# MotorDriverPCB.net
KiCad netlist of a schematic drawn in Altium Designer
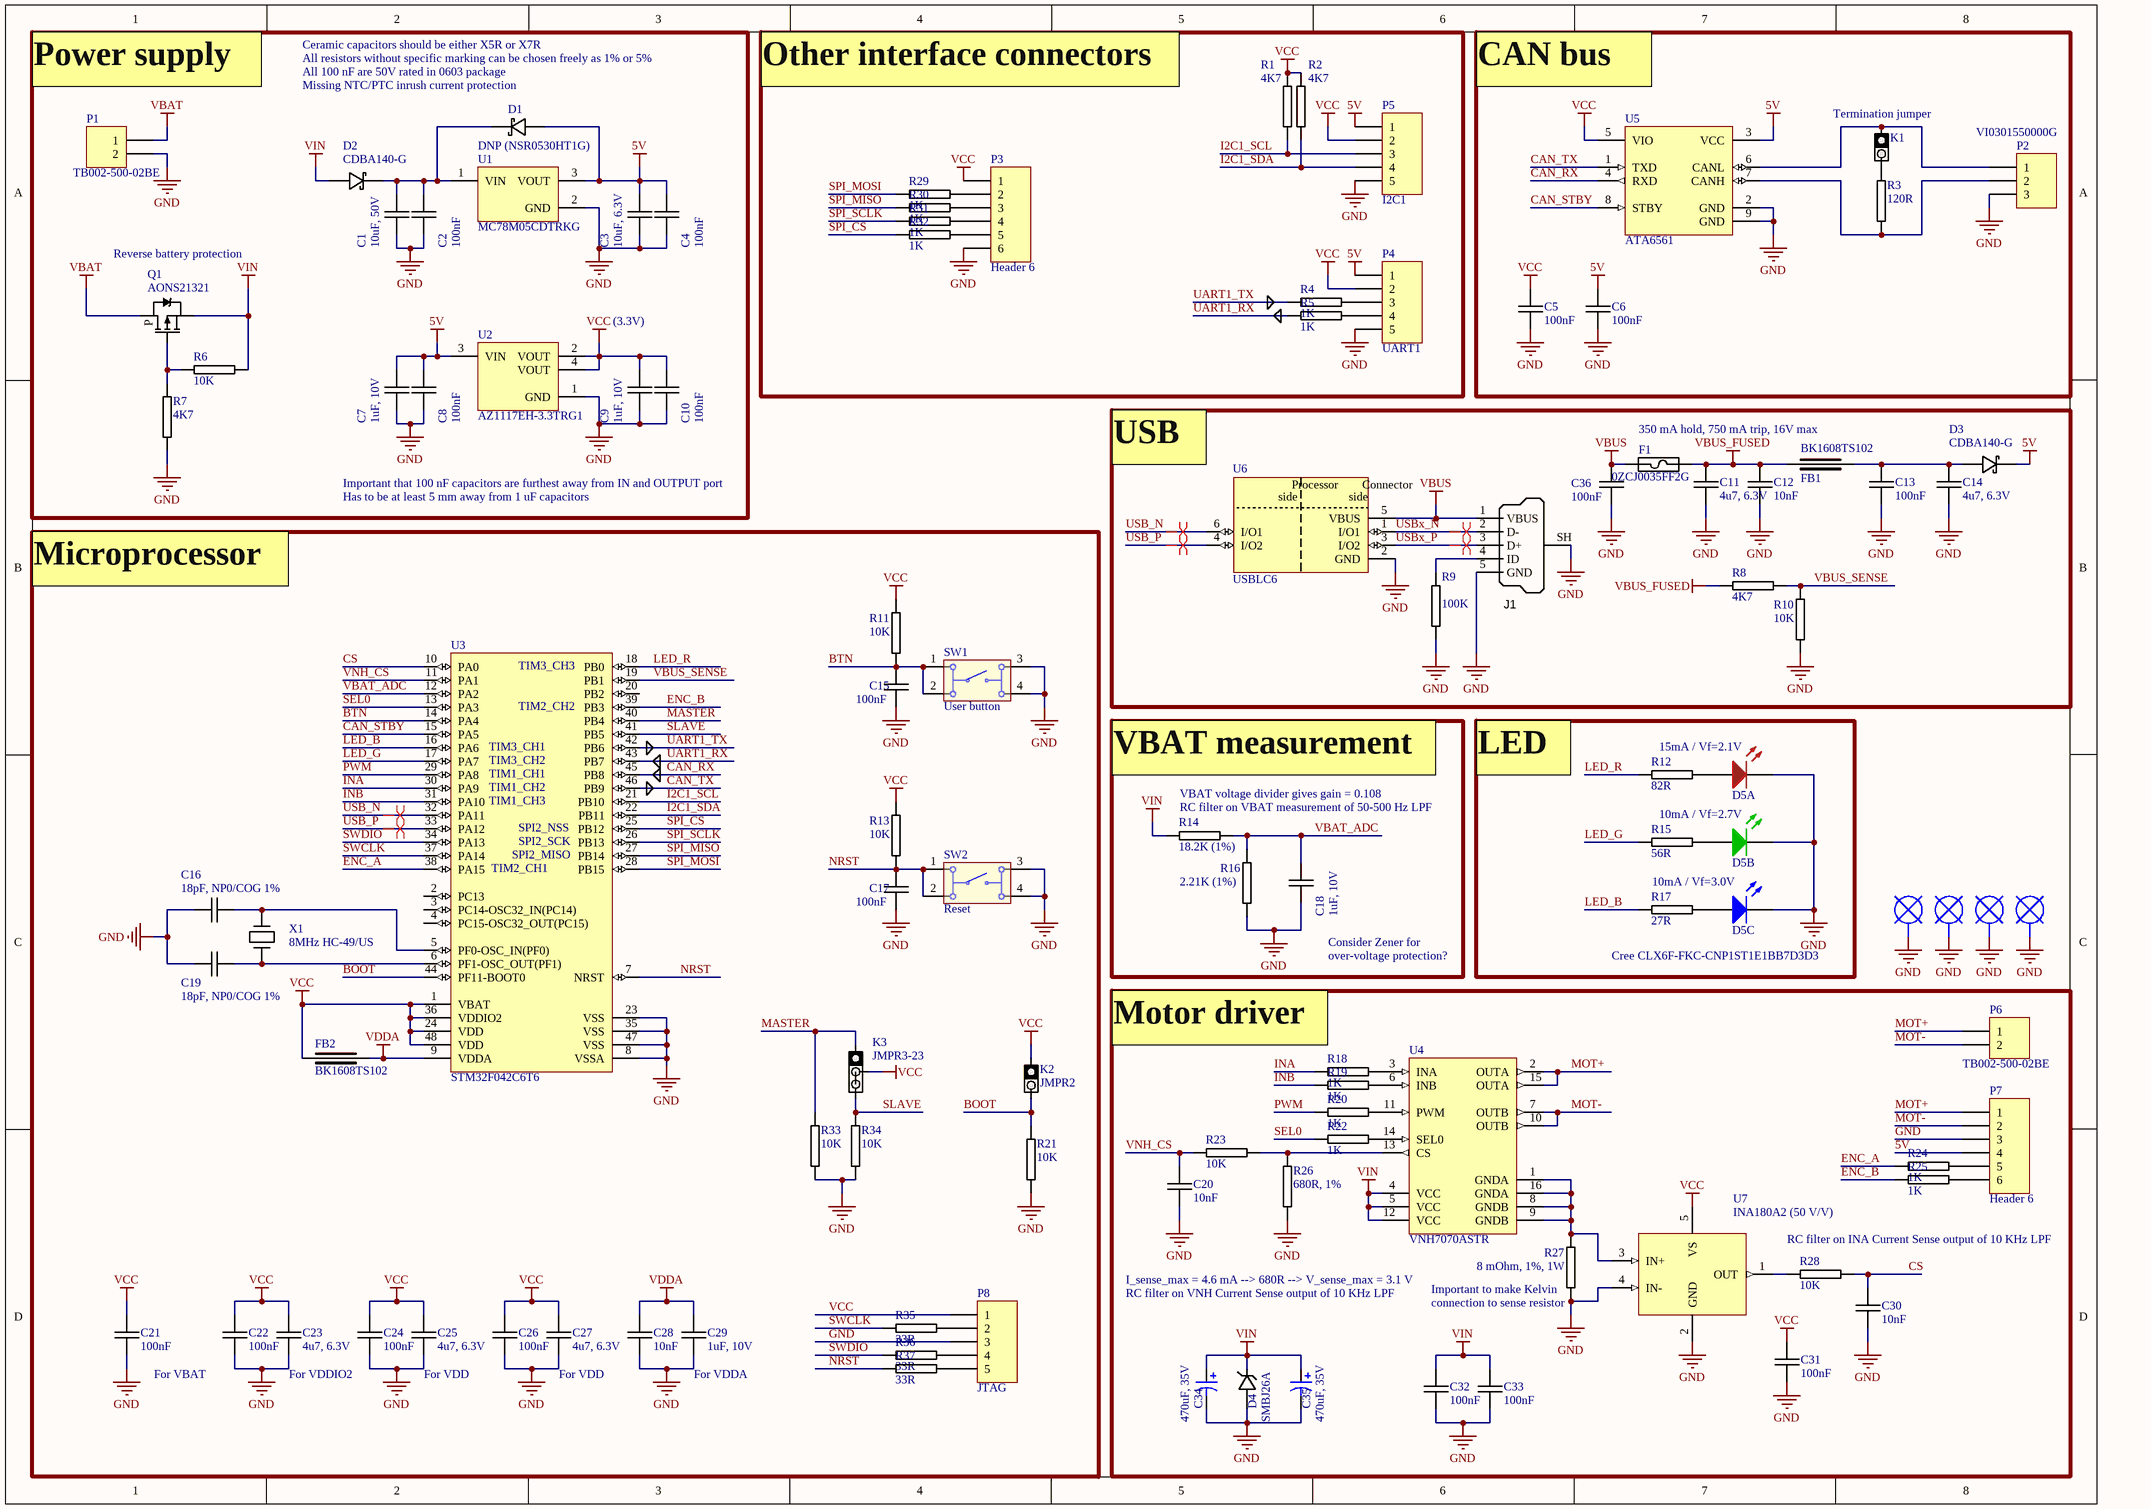
[diagram p0: MotorDriverPCB.SchDoc]

(export (version "E")
  (design (tool "Eeschema 10.0.6"))
  (components
    (comp (ref "C1")
      (value "10uF, 50V")
      (footprint "1206C-GENERIC")
      (description "CAP CER 10UF 35V Y5V 1206")
      (fields (field (name "MANUFACTURER PART NUMBER") "GMK316F106ZL-T"))
      (libsource (lib "vh_Altium Library") (part "1206C-10U-35V-X7R"))
    )
    (comp (ref "C2")
      (value "100nF")
      (footprint "0603C-GENERIC")
      (description "CAP CER .10UF 25V X7R 10% 0603")
      (fields (field (name "MANUFACTURER PART NUMBER") "C1608X7R1E104K"))
      (libsource (lib "vh_Altium Library") (part "0603C-100NF-25V-X7R-TDK"))
    )
    (comp (ref "C3")
      (value "10uF, 6.3V")
      (footprint "0805C-GENERIC")
      (description "CAP 10UF 6.3V CERAMIC X5R 0805")
      (fields (field (name "TOLERANCE") "±20%"))
      (libsource (lib "vh_Altium Library") (part "0805C-10UF-6V3-X5R-PAN"))
    )
    (comp (ref "C4")
      (value "100nF")
      (footprint "0603C-GENERIC")
      (description "CAP CER .10UF 25V X7R 10% 0603")
      (fields (field (name "MANUFACTURER PART NUMBER") "C1608X7R1E104K"))
      (libsource (lib "vh_Altium Library") (part "0603C-100NF-25V-X7R-TDK"))
    )
    (comp (ref "C5")
      (value "100nF")
      (footprint "0603C-GENERIC")
      (description "CAP CER .10UF 25V X7R 10% 0603")
      (fields (field (name "MANUFACTURER PART NUMBER") "C1608X7R1E104K"))
      (libsource (lib "vh_Altium Library") (part "0603C-100NF-25V-X7R-TDK"))
    )
    (comp (ref "C6")
      (value "100nF")
      (footprint "0603C-GENERIC")
      (description "CAP CER .10UF 25V X7R 10% 0603")
      (fields (field (name "MANUFACTURER PART NUMBER") "C1608X7R1E104K"))
      (libsource (lib "vh_Altium Library") (part "0603C-100NF-25V-X7R-TDK"))
    )
    (comp (ref "C7")
      (value "1uF, 10V")
      (footprint "0603C-GENERIC")
      (description "CAP CER 1.0UF 35V X5R 0603")
      (fields (field (name "MANUFACTURER PART NUMBER") "GMK107BJ105KA-T"))
      (libsource (lib "vh_Altium Library") (part "0603C-1UF-35V-X5R-TAY"))
    )
    (comp (ref "C8")
      (value "100nF")
      (footprint "0603C-GENERIC")
      (description "CAP CER .10UF 25V X7R 10% 0603")
      (fields (field (name "MANUFACTURER PART NUMBER") "C1608X7R1E104K"))
      (libsource (lib "vh_Altium Library") (part "0603C-100NF-25V-X7R-TDK"))
    )
    (comp (ref "C9")
      (value "1uF, 10V")
      (footprint "0603C-GENERIC")
      (description "CAP CER 1.0UF 35V X5R 0603")
      (fields (field (name "MANUFACTURER PART NUMBER") "GMK107BJ105KA-T"))
      (libsource (lib "vh_Altium Library") (part "0603C-1UF-35V-X5R-TAY"))
    )
    (comp (ref "C10")
      (value "100nF")
      (footprint "0603C-GENERIC")
      (description "CAP CER .10UF 25V X7R 10% 0603")
      (fields (field (name "MANUFACTURER PART NUMBER") "C1608X7R1E104K"))
      (libsource (lib "vh_Altium Library") (part "0603C-100NF-25V-X7R-TDK"))
    )
    (comp (ref "C11")
      (value "4u7, 6.3V")
      (footprint "0603C-GENERIC")
      (description "GENERIC CAPACITOR NON POLARISED 0603")
      (libsource (lib "vh_Altium Library") (part "0603C-4U7-6V3-X5R-KEM"))
    )
    (comp (ref "C12")
      (value "10nF")
      (footprint "0603C-GENERIC")
      (description "GENERIC CAPACITOR NON POLARISED 0603")
      (fields
        (field (name "MANUFACTURER PART NUMBER") "GRM188R71H103KA01D")
        (field (name "MANUFACTURER") "Murata Electronics North America")
      )
      (libsource (lib "vh_Altium Library") (part "0603C-10NF-50V-X7R-MUR"))
    )
    (comp (ref "C13")
      (value "100nF")
      (footprint "0603C-GENERIC")
      (description "CAP CER .10UF 25V X7R 10% 0603")
      (fields (field (name "MANUFACTURER PART NUMBER") "C1608X7R1E104K"))
      (libsource (lib "vh_Altium Library") (part "0603C-100NF-25V-X7R-TDK"))
    )
    (comp (ref "C14")
      (value "4u7, 6.3V")
      (footprint "0603C-GENERIC")
      (description "GENERIC CAPACITOR NON POLARISED 0603")
      (libsource (lib "vh_Altium Library") (part "0603C-4U7-6V3-X5R-KEM"))
    )
    (comp (ref "C15")
      (value "100nF")
      (footprint "0603C-GENERIC")
      (description "CAP CER .10UF 25V X7R 10% 0603")
      (fields (field (name "MANUFACTURER PART NUMBER") "C1608X7R1E104K"))
      (libsource (lib "vh_Altium Library") (part "0603C-100NF-25V-X7R-TDK"))
    )
    (comp (ref "C16")
      (value "18pF, NP0/COG 1%")
      (footprint "0603C-GENERIC")
      (description "GENERIC CAPACITOR NON POLARISED 0603")
      (libsource (lib "vh_Altium Library") (part "0603C-15PF-50V-C0G-MUR"))
    )
    (comp (ref "C17")
      (value "100nF")
      (footprint "0603C-GENERIC")
      (description "CAP CER .10UF 25V X7R 10% 0603")
      (fields (field (name "MANUFACTURER PART NUMBER") "C1608X7R1E104K"))
      (libsource (lib "vh_Altium Library") (part "0603C-100NF-25V-X7R-TDK"))
    )
    (comp (ref "C18")
      (value "1uF, 10V")
      (footprint "0603C-GENERIC")
      (description "CAP CER 1.0UF 35V X5R 0603")
      (fields (field (name "MANUFACTURER PART NUMBER") "GMK107BJ105KA-T"))
      (libsource (lib "vh_Altium Library") (part "0603C-1UF-35V-X5R-TAY"))
    )
    (comp (ref "C19")
      (value "18pF, NP0/COG 1%")
      (footprint "0603C-GENERIC")
      (description "GENERIC CAPACITOR NON POLARISED 0603")
      (libsource (lib "vh_Altium Library") (part "0603C-15PF-50V-C0G-MUR"))
    )
    (comp (ref "C20")
      (value "10nF")
      (footprint "0603C-GENERIC")
      (description "GENERIC CAPACITOR NON POLARISED 0603")
      (fields
        (field (name "MANUFACTURER PART NUMBER") "GRM188R71H103KA01D")
        (field (name "MANUFACTURER") "Murata Electronics North America")
      )
      (libsource (lib "vh_Altium Library") (part "0603C-10NF-50V-X7R-MUR"))
    )
    (comp (ref "C21")
      (value "100nF")
      (footprint "0603C-GENERIC")
      (description "CAP CER .10UF 25V X7R 10% 0603")
      (fields (field (name "MANUFACTURER PART NUMBER") "C1608X7R1E104K"))
      (libsource (lib "vh_Altium Library") (part "0603C-100NF-25V-X7R-TDK"))
    )
    (comp (ref "C22")
      (value "100nF")
      (footprint "0603C-GENERIC")
      (description "CAP CER .10UF 25V X7R 10% 0603")
      (fields (field (name "MANUFACTURER PART NUMBER") "C1608X7R1E104K"))
      (libsource (lib "vh_Altium Library") (part "0603C-100NF-25V-X7R-TDK"))
    )
    (comp (ref "C23")
      (value "4u7, 6.3V")
      (footprint "0603C-GENERIC")
      (description "GENERIC CAPACITOR NON POLARISED 0603")
      (libsource (lib "vh_Altium Library") (part "0603C-4U7-6V3-X5R-KEM"))
    )
    (comp (ref "C24")
      (value "100nF")
      (footprint "0603C-GENERIC")
      (description "CAP CER .10UF 25V X7R 10% 0603")
      (fields (field (name "MANUFACTURER PART NUMBER") "C1608X7R1E104K"))
      (libsource (lib "vh_Altium Library") (part "0603C-100NF-25V-X7R-TDK"))
    )
    (comp (ref "C25")
      (value "4u7, 6.3V")
      (footprint "0603C-GENERIC")
      (description "GENERIC CAPACITOR NON POLARISED 0603")
      (libsource (lib "vh_Altium Library") (part "0603C-4U7-6V3-X5R-KEM"))
    )
    (comp (ref "C26")
      (value "100nF")
      (footprint "0603C-GENERIC")
      (description "CAP CER .10UF 25V X7R 10% 0603")
      (fields (field (name "MANUFACTURER PART NUMBER") "C1608X7R1E104K"))
      (libsource (lib "vh_Altium Library") (part "0603C-100NF-25V-X7R-TDK"))
    )
    (comp (ref "C27")
      (value "4u7, 6.3V")
      (footprint "0603C-GENERIC")
      (description "GENERIC CAPACITOR NON POLARISED 0603")
      (libsource (lib "vh_Altium Library") (part "0603C-4U7-6V3-X5R-KEM"))
    )
    (comp (ref "C28")
      (value "10nF")
      (footprint "0603C-GENERIC")
      (description "GENERIC CAPACITOR NON POLARISED 0603")
      (fields
        (field (name "MANUFACTURER PART NUMBER") "GRM188R71H103KA01D")
        (field (name "MANUFACTURER") "Murata Electronics North America")
      )
      (libsource (lib "vh_Altium Library") (part "0603C-10NF-50V-X7R-MUR"))
    )
    (comp (ref "C29")
      (value "1uF, 10V")
      (footprint "0603C-GENERIC")
      (description "CAP CER 1.0UF 35V X5R 0603")
      (fields (field (name "MANUFACTURER PART NUMBER") "GMK107BJ105KA-T"))
      (libsource (lib "vh_Altium Library") (part "0603C-1UF-35V-X5R-TAY"))
    )
    (comp (ref "C30")
      (value "10nF")
      (footprint "0603C-GENERIC")
      (description "GENERIC CAPACITOR NON POLARISED 0603")
      (fields
        (field (name "MANUFACTURER PART NUMBER") "GRM188R71H103KA01D")
        (field (name "MANUFACTURER") "Murata Electronics North America")
      )
      (libsource (lib "vh_Altium Library") (part "0603C-10NF-50V-X7R-MUR"))
    )
    (comp (ref "C31")
      (value "100nF")
      (footprint "0603C-GENERIC")
      (description "CAP CER .10UF 25V X7R 10% 0603")
      (fields (field (name "MANUFACTURER PART NUMBER") "C1608X7R1E104K"))
      (libsource (lib "vh_Altium Library") (part "0603C-100NF-25V-X7R-TDK"))
    )
    (comp (ref "C32")
      (value "100nF")
      (footprint "0603C-GENERIC")
      (description "CAP CER .10UF 25V X7R 10% 0603")
      (fields (field (name "MANUFACTURER PART NUMBER") "C1608X7R1E104K"))
      (libsource (lib "vh_Altium Library") (part "0603C-100NF-25V-X7R-TDK"))
    )
    (comp (ref "C33")
      (value "100nF")
      (footprint "0603C-GENERIC")
      (description "CAP CER .10UF 25V X7R 10% 0603")
      (fields (field (name "MANUFACTURER PART NUMBER") "C1608X7R1E104K"))
      (libsource (lib "vh_Altium Library") (part "0603C-100NF-25V-X7R-TDK"))
    )
    (comp (ref "C34")
      (value "470uF, 35V")
      (footprint "SMT_10x10.5")
      (description "Surface mount, Polarized Electrolytic Aluminum Capacitor")
      (libsource (lib "AluminumCapacitors") (part "AluCap_SMT"))
    )
    (comp (ref "C35")
      (value "470uF, 35V")
      (footprint "SMT_10x10.5")
      (description "Surface mount, Polarized Electrolytic Aluminum Capacitor")
      (libsource (lib "AluminumCapacitors") (part "AluCap_SMT"))
    )
    (comp (ref "C36")
      (value "100nF")
      (footprint "0603C-GENERIC")
      (description "CAP CER .10UF 25V X7R 10% 0603")
      (fields (field (name "MANUFACTURER PART NUMBER") "C1608X7R1E104K"))
      (libsource (lib "vh_Altium Library") (part "0603C-100NF-25V-X7R-TDK"))
    )
    (comp (ref "D1")
      (value "DNP (NSR0530HT1G)")
      (footprint "SOD323")
      (description "Diode Schottky")
      (libsource (lib "Components") (part "DIODE_SCHOTTKY"))
    )
    (comp (ref "D2")
      (value "CDBA140-G")
      (footprint "DO-214AC-SMA")
      (description "Diode Schottky")
      (libsource (lib "Components") (part "DIODE_SCHOTTKY"))
    )
    (comp (ref "D3")
      (value "CDBA140-G")
      (footprint "DO-214AC-SMA")
      (description "Diode Schottky")
      (libsource (lib "Components") (part "DIODE_SCHOTTKY"))
    )
    (comp (ref "D4")
      (value "SMBJ26A")
      (footprint "DO-214AA")
      (description "Diode SMD Transil")
      (libsource (lib "Components") (part "DIODE_TVS"))
    )
    (comp (ref "D5")
      (value "LED RGB Individual")
      (footprint "LED-3535-6")
      (libsource (lib "Components") (part "LED RGB Individual"))
    )
    (comp (ref "F1")
      (value "0ZCJ0035FF2G")
      (footprint "1206C-GENERIC")
      (description "PTC Resettable Fuse")
      (libsource (lib "Components") (part "FUSE-PTC"))
    )
    (comp (ref "FB1")
      (value "BK1608TS102")
      (footprint "0603FB-GENERIC")
      (description "FERRITE BEAD SMD")
      (libsource (lib "vh_Altium Library") (part "0603FB-GENERIC"))
    )
    (comp (ref "FB2")
      (value "BK1608TS102")
      (footprint "0603FB-GENERIC")
      (description "FERRITE BEAD SMD")
      (libsource (lib "vh_Altium Library") (part "0603FB-GENERIC"))
    )
    (comp (ref "H1")
      (value "SCREW-HOLE")
      (footprint "Screw-hole-3mm")
      (description "PCB Screw hole")
      (libsource (lib "Components") (part "SCREW-HOLE"))
    )
    (comp (ref "H2")
      (value "SCREW-HOLE")
      (footprint "Screw-hole-3mm")
      (description "PCB Screw hole")
      (libsource (lib "Components") (part "SCREW-HOLE"))
    )
    (comp (ref "H3")
      (value "SCREW-HOLE")
      (footprint "Screw-hole-3mm")
      (description "PCB Screw hole")
      (libsource (lib "Components") (part "SCREW-HOLE"))
    )
    (comp (ref "H4")
      (value "SCREW-HOLE")
      (footprint "Screw-hole-3mm")
      (description "PCB Screw hole")
      (libsource (lib "Components") (part "SCREW-HOLE"))
    )
    (comp (ref "J1")
      (value "USB Type B")
      (footprint "USB-MINI-B")
      (description "Connector SMD-THD USB Type B middle mount")
      (libsource (lib "Components") (part "USB-Type-B"))
    )
    (comp (ref "K1")
      (value "JMPR2")
      (footprint "JMPR2")
      (description "CONN HEADER .100 SINGL STR 36POS")
      (fields (field (name "MANUFACTURER") "Sullins Connector Solutions"))
      (libsource (lib "vh_Altium Library") (part "JMPR2"))
    )
    (comp (ref "K2")
      (value "JMPR2")
      (footprint "JMPR2")
      (description "CONN HEADER .100 SINGL STR 36POS")
      (fields (field (name "MANUFACTURER") "Sullins Connector Solutions"))
      (libsource (lib "vh_Altium Library") (part "JMPR2"))
    )
    (comp (ref "K3")
      (value "JMPR3-23")
      (footprint "JMPR3-CLOSED-23")
      (description "CONN HEADER .100 SINGL STR 36POS")
      (fields (field (name "MANUFACTURER") "Sullins Connector Solutions"))
      (libsource (lib "vh_Altium Library") (part "JMPR3-23"))
    )
    (comp (ref "P1")
      (value "TB002-500-02BE")
      (footprint "SCREW-2-5mm")
      (description "Screw terminal, 2-pin, 5mm pitch")
      (libsource (lib "") (part "SCREW-2_1"))
    )
    (comp (ref "P2")
      (value "VI0301550000G")
      (footprint "SCREW-3-5mm")
      (description "Screw terminal, 3-pin, 5mm pitch")
      (libsource (lib "Components") (part "SCREW-3"))
    )
    (comp (ref "P3")
      (value "Header 6")
      (footprint "HEADER-1X6")
      (description "Header, 6-Pin")
      (fields (field (name "PUBLISHER") "Altium Limited"))
      (libsource (lib "Components") (part "Header 6"))
    )
    (comp (ref "P4")
      (value "UART1")
      (footprint "HEADER-1X5")
      (description "Header, 5-Pin")
      (libsource (lib "Components") (part "Header 5"))
    )
    (comp (ref "P5")
      (value "I2C1")
      (footprint "HEADER-1X5")
      (description "Header, 5-Pin")
      (libsource (lib "Components") (part "Header 5"))
    )
    (comp (ref "P6")
      (value "TB002-500-02BE")
      (footprint "SCREW-2-5mm")
      (description "Screw terminal, 2-pin, 5mm pitch")
      (libsource (lib "Components") (part "SCREW-2"))
    )
    (comp (ref "P7")
      (value "Header 6")
      (footprint "HEADER-1X6")
      (description "Header, 6-Pin")
      (fields (field (name "PUBLISHER") "Altium Limited"))
      (libsource (lib "Components") (part "Header 6"))
    )
    (comp (ref "P8")
      (value "JTAG")
      (footprint "HEADER-1X5")
      (description "Header, 5-Pin")
      (libsource (lib "Components") (part "Header 5"))
    )
    (comp (ref "Q1")
      (value "AONS21321")
      (footprint "SO8FL-DFN5x6")
      (description "P-Channel MOSFET")
      (fields (field (name "PUBLISHER") "Altium Limited"))
      (libsource (lib "Components") (part "MOSFET-P"))
    )
    (comp (ref "R1")
      (value "4K7")
      (footprint "0603R-4K7")
      (description "GENERIC RESISTOR 0603")
      (fields
        (field (name "MANUFACTURER") "Stackpole Electronics Inc")
        (field (name "MANUFACTURER PART NUMBER") "RMCF 1/16 4.7K 1% R")
      )
      (libsource (lib "vh_Altium Library") (part "0603R-4K7"))
    )
    (comp (ref "R2")
      (value "4K7")
      (footprint "0603R-4K7")
      (description "GENERIC RESISTOR 0603")
      (fields
        (field (name "MANUFACTURER") "Stackpole Electronics Inc")
        (field (name "MANUFACTURER PART NUMBER") "RMCF 1/16 4.7K 1% R")
      )
      (libsource (lib "vh_Altium Library") (part "0603R-4K7"))
    )
    (comp (ref "R3")
      (value "120R")
      (footprint "0603R-120")
      (description "RES TF 1/10W 120 OHM 1% 0603")
      (fields (field (name "TOLERANCE") "±1%"))
      (libsource (lib "vh_Altium Library") (part "0603R-120"))
    )
    (comp (ref "R4")
      (value "1K")
      (footprint "0603R-1k")
      (description "GENERIC RESISTOR 0603")
      (fields
        (field (name "MANUFACTURER PART NUMBER") "RMCF 1/16 1K 1% R")
        (field (name "MANUFACTURER") "Stackpole Electronics Inc")
      )
      (libsource (lib "vh_Altium Library") (part "0603R-1K"))
    )
    (comp (ref "R5")
      (value "1K")
      (footprint "0603R-1k")
      (description "GENERIC RESISTOR 0603")
      (fields
        (field (name "MANUFACTURER PART NUMBER") "RMCF 1/16 1K 1% R")
        (field (name "MANUFACTURER") "Stackpole Electronics Inc")
      )
      (libsource (lib "vh_Altium Library") (part "0603R-1K"))
    )
    (comp (ref "R6")
      (value "10K")
      (footprint "0603R-10K")
      (description "GENERIC RESISTOR 0603")
      (fields (field (name "MANUFACTURER") "Stackpole Electronics Inc") (field (name "TOLERANCE") "±1%"))
      (libsource (lib "vh_Altium Library") (part "0603R-10K"))
    )
    (comp (ref "R7")
      (value "4K7")
      (footprint "0603R-4K7")
      (description "GENERIC RESISTOR 0603")
      (fields
        (field (name "MANUFACTURER") "Stackpole Electronics Inc")
        (field (name "MANUFACTURER PART NUMBER") "RMCF 1/16 4.7K 1% R")
      )
      (libsource (lib "vh_Altium Library") (part "0603R-4K7"))
    )
    (comp (ref "R8")
      (value "4K7")
      (footprint "0603R-4K7")
      (description "GENERIC RESISTOR 0603")
      (fields
        (field (name "MANUFACTURER") "Stackpole Electronics Inc")
        (field (name "MANUFACTURER PART NUMBER") "RMCF 1/16 4.7K 1% R")
      )
      (libsource (lib "vh_Altium Library") (part "0603R-4K7"))
    )
    (comp (ref "R9")
      (value "100K")
      (footprint "0603R-100K")
      (description "GENERIC RESISTOR 0603")
      (fields
        (field (name "TOLERANCE") "±1%")
        (field (name "MANUFACTURER PART NUMBER") "RMCF 1/16 100K 1% R")
      )
      (libsource (lib "vh_Altium Library") (part "0603R-100K"))
    )
    (comp (ref "R10")
      (value "10K")
      (footprint "0603R-10K")
      (description "GENERIC RESISTOR 0603")
      (fields (field (name "MANUFACTURER") "Stackpole Electronics Inc") (field (name "TOLERANCE") "±1%"))
      (libsource (lib "vh_Altium Library") (part "0603R-10K"))
    )
    (comp (ref "R11")
      (value "10K")
      (footprint "0603R-10K")
      (description "GENERIC RESISTOR 0603")
      (fields (field (name "MANUFACTURER") "Stackpole Electronics Inc") (field (name "TOLERANCE") "±1%"))
      (libsource (lib "vh_Altium Library") (part "0603R-10K"))
    )
    (comp (ref "R12")
      (value "82R")
      (footprint "0603R-82")
      (description "GENERIC RESISTOR 0603")
      (fields
        (field (name "MANUFACTURER") "Stackpole Electronics Inc")
        (field (name "MANUFACTURER PART NUMBER") "RMC 1/16 82 1% R")
      )
      (libsource (lib "vh_Altium Library") (part "0603R-82R"))
    )
    (comp (ref "R13")
      (value "10K")
      (footprint "0603R-10K")
      (description "GENERIC RESISTOR 0603")
      (fields (field (name "MANUFACTURER") "Stackpole Electronics Inc") (field (name "TOLERANCE") "±1%"))
      (libsource (lib "vh_Altium Library") (part "0603R-10K"))
    )
    (comp (ref "R14")
      (value "18.2K (1%)")
      (footprint "0603R-18K")
      (description "GENERIC RESISTOR 0603")
      (fields (field (name "TOLERANCE") "±1%") (field (name "MANUFACTURER PART NUMBER") "RMC 1/16 18K 1% R"))
      (libsource (lib "vh_Altium Library") (part "0603R-18K"))
    )
    (comp (ref "R15")
      (value "56R")
      (footprint "0603R-56")
      (description "GENERIC RESISTOR 0603")
      (fields
        (field (name "MANUFACTURER") "Stackpole Electronics Inc")
        (field (name "MANUFACTURER PART NUMBER") "RMC 1/16 56 1% R")
      )
      (libsource (lib "vh_Altium Library") (part "0603R-56R"))
    )
    (comp (ref "R16")
      (value "2.21K (1%)")
      (footprint "0603R-2K2")
      (description "RES TF 1/10W 2.2K OHM 1% 0603")
      (fields (field (name "MANUFACTURER PART NUMBER") "RMC 1/16 2.2K 1% R"))
      (libsource (lib "vh_Altium Library") (part "0603R-2K2"))
    )
    (comp (ref "R17")
      (value "27R")
      (footprint "0603R-27")
      (description "RES TF 1/10W 27 OHM 1% 0603")
      (fields (field (name "TOLERANCE") "±1%"))
      (libsource (lib "vh_Altium Library") (part "0603R-27R"))
    )
    (comp (ref "R18")
      (value "1K")
      (footprint "0603R-1k")
      (description "GENERIC RESISTOR 0603")
      (fields
        (field (name "MANUFACTURER PART NUMBER") "RMCF 1/16 1K 1% R")
        (field (name "MANUFACTURER") "Stackpole Electronics Inc")
      )
      (libsource (lib "vh_Altium Library") (part "0603R-1K"))
    )
    (comp (ref "R19")
      (value "1K")
      (footprint "0603R-1k")
      (description "GENERIC RESISTOR 0603")
      (fields
        (field (name "MANUFACTURER PART NUMBER") "RMCF 1/16 1K 1% R")
        (field (name "MANUFACTURER") "Stackpole Electronics Inc")
      )
      (libsource (lib "vh_Altium Library") (part "0603R-1K"))
    )
    (comp (ref "R20")
      (value "1K")
      (footprint "0603R-1k")
      (description "GENERIC RESISTOR 0603")
      (fields
        (field (name "MANUFACTURER PART NUMBER") "RMCF 1/16 1K 1% R")
        (field (name "MANUFACTURER") "Stackpole Electronics Inc")
      )
      (libsource (lib "vh_Altium Library") (part "0603R-1K"))
    )
    (comp (ref "R21")
      (value "10K")
      (footprint "0603R-10K")
      (description "GENERIC RESISTOR 0603")
      (fields (field (name "MANUFACTURER") "Stackpole Electronics Inc") (field (name "TOLERANCE") "±1%"))
      (libsource (lib "vh_Altium Library") (part "0603R-10K"))
    )
    (comp (ref "R22")
      (value "1K")
      (footprint "0603R-1k")
      (description "GENERIC RESISTOR 0603")
      (fields
        (field (name "MANUFACTURER PART NUMBER") "RMCF 1/16 1K 1% R")
        (field (name "MANUFACTURER") "Stackpole Electronics Inc")
      )
      (libsource (lib "vh_Altium Library") (part "0603R-1K"))
    )
    (comp (ref "R23")
      (value "10K")
      (footprint "0603R-10K")
      (description "GENERIC RESISTOR 0603")
      (fields (field (name "MANUFACTURER") "Stackpole Electronics Inc") (field (name "TOLERANCE") "±1%"))
      (libsource (lib "vh_Altium Library") (part "0603R-10K"))
    )
    (comp (ref "R24")
      (value "1K")
      (footprint "0603R-1k")
      (description "GENERIC RESISTOR 0603")
      (fields
        (field (name "MANUFACTURER PART NUMBER") "RMCF 1/16 1K 1% R")
        (field (name "MANUFACTURER") "Stackpole Electronics Inc")
      )
      (libsource (lib "vh_Altium Library") (part "0603R-1K"))
    )
    (comp (ref "R25")
      (value "1K")
      (footprint "0603R-1k")
      (description "GENERIC RESISTOR 0603")
      (fields
        (field (name "MANUFACTURER PART NUMBER") "RMCF 1/16 1K 1% R")
        (field (name "MANUFACTURER") "Stackpole Electronics Inc")
      )
      (libsource (lib "vh_Altium Library") (part "0603R-1K"))
    )
    (comp (ref "R26")
      (value "680R, 1%")
      (footprint "0603R-680")
      (description "RES TF 1/10W 680 OHM 1% 0603")
      (fields (field (name "MANUFACTURER PART NUMBER") "RMC 1/16 680 1% R"))
      (libsource (lib "vh_Altium Library") (part "0603R-680"))
    )
    (comp (ref "R27")
      (value "8 mOhm, 1%, 1W")
      (footprint "2512R-GENERIC")
      (description "POWER RESISTOR 2512")
      (libsource (lib "Components") (part "2512R"))
    )
    (comp (ref "R28")
      (value "10K")
      (footprint "0603R-10K")
      (description "GENERIC RESISTOR 0603")
      (fields (field (name "MANUFACTURER") "Stackpole Electronics Inc") (field (name "TOLERANCE") "±1%"))
      (libsource (lib "vh_Altium Library") (part "0603R-10K"))
    )
    (comp (ref "R29")
      (value "1K")
      (footprint "0603R-1k")
      (description "GENERIC RESISTOR 0603")
      (fields
        (field (name "MANUFACTURER PART NUMBER") "RMCF 1/16 1K 1% R")
        (field (name "MANUFACTURER") "Stackpole Electronics Inc")
      )
      (libsource (lib "vh_Altium Library") (part "0603R-1K"))
    )
    (comp (ref "R30")
      (value "1K")
      (footprint "0603R-1k")
      (description "GENERIC RESISTOR 0603")
      (fields
        (field (name "MANUFACTURER PART NUMBER") "RMCF 1/16 1K 1% R")
        (field (name "MANUFACTURER") "Stackpole Electronics Inc")
      )
      (libsource (lib "vh_Altium Library") (part "0603R-1K"))
    )
    (comp (ref "R31")
      (value "1K")
      (footprint "0603R-1k")
      (description "GENERIC RESISTOR 0603")
      (fields
        (field (name "MANUFACTURER PART NUMBER") "RMCF 1/16 1K 1% R")
        (field (name "MANUFACTURER") "Stackpole Electronics Inc")
      )
      (libsource (lib "vh_Altium Library") (part "0603R-1K"))
    )
    (comp (ref "R32")
      (value "1K")
      (footprint "0603R-1k")
      (description "GENERIC RESISTOR 0603")
      (fields
        (field (name "MANUFACTURER PART NUMBER") "RMCF 1/16 1K 1% R")
        (field (name "MANUFACTURER") "Stackpole Electronics Inc")
      )
      (libsource (lib "vh_Altium Library") (part "0603R-1K"))
    )
    (comp (ref "R33")
      (value "10K")
      (footprint "0603R-10K")
      (description "GENERIC RESISTOR 0603")
      (fields (field (name "MANUFACTURER") "Stackpole Electronics Inc") (field (name "TOLERANCE") "±1%"))
      (libsource (lib "vh_Altium Library") (part "0603R-10K"))
    )
    (comp (ref "R34")
      (value "10K")
      (footprint "0603R-10K")
      (description "GENERIC RESISTOR 0603")
      (fields (field (name "MANUFACTURER") "Stackpole Electronics Inc") (field (name "TOLERANCE") "±1%"))
      (libsource (lib "vh_Altium Library") (part "0603R-10K"))
    )
    (comp (ref "R35")
      (value "33R")
      (footprint "0603R-33")
      (description "RES TF 1/10W 33 OHM 1% 0603")
      (fields (field (name "MANUFACTURER PART NUMBER") "RMC 1/16 33 1% G"))
      (libsource (lib "vh_Altium Library") (part "0603R-33"))
    )
    (comp (ref "R36")
      (value "33R")
      (footprint "0603R-33")
      (description "RES TF 1/10W 33 OHM 1% 0603")
      (fields (field (name "MANUFACTURER PART NUMBER") "RMC 1/16 33 1% G"))
      (libsource (lib "vh_Altium Library") (part "0603R-33"))
    )
    (comp (ref "R37")
      (value "33R")
      (footprint "0603R-33")
      (description "RES TF 1/10W 33 OHM 1% 0603")
      (fields (field (name "MANUFACTURER PART NUMBER") "RMC 1/16 33 1% G"))
      (libsource (lib "vh_Altium Library") (part "0603R-33"))
    )
    (comp (ref "SW1")
      (value "User button")
      (footprint "TACT-TH-6x6")
      (description "Tactile Switch")
      (libsource (lib "Components") (part "Tactile Switch"))
    )
    (comp (ref "SW2")
      (value "Reset")
      (footprint "TACT-TH-6x6")
      (description "Tactile Switch")
      (libsource (lib "Components") (part "Tactile Switch"))
    )
    (comp (ref "U1")
      (value "MC78M05CDTRKG")
      (footprint "DPAK")
      (description "5V, 500mA, LDO Regulator, 3-Pin DDPAK")
      (libsource (lib "Components") (part "MC78M05CDTRKG"))
    )
    (comp (ref "U2")
      (value "AZ1117EH-3.3TRG1")
      (footprint "SOT-223")
      (description "3.3V, 1A, LDO Regulator, 3-Pin SOT-223")
      (libsource (lib "Components") (part "AZ1117EH-3.3TRG1"))
    )
    (comp (ref "U3")
      (value "STM32F042C6T6")
      (footprint "STM-LQFP48_N")
      (description "IC MCU 32BIT 32KB FLASH 48LQFP")
      (libsource (lib "Components") (part "STM32F042C6T6"))
    )
    (comp (ref "U4")
      (value "VNH7070ASTR")
      (footprint "STM-SO-16N_M")
      (description "SO 16 .15 TO JEDEC MS-012")
      (libsource (lib "Components") (part "VNH7070ASTR"))
    )
    (comp (ref "U5")
      (value "ATA6561")
      (footprint "VDFN8")
      (description "High-Speed CAN Transceiver with Standby Mode  CAN FD Ready")
      (libsource (lib "Components") (part "ATA6561"))
    )
    (comp (ref "U6")
      (value "USBLC6")
      (footprint "SOT23-6")
      (description "Very low capacitance ESD protection")
      (libsource (lib "Components") (part "USBLC6"))
    )
    (comp (ref "U7")
      (value "INA180A2 (50 V/V)")
      (footprint "SOT23-5")
      (description "INAx180 Low- and high-side voltage output, current-sense amplifiers")
      (libsource (lib "Components") (part "INA180A"))
    )
    (comp (ref "X1")
      (value "8MHz HC-49/US")
      (footprint "HC-49/US")
      (description "HC-49/US")
      (libsource (lib "Components") (part "HC-49/US"))
    )
  )
  (nets
    (net (code "1") (name "/BOOT") (class "Default")
      (node (ref "K2") (pin "2") (pintype "passive"))
      (node (ref "R21") (pin "2") (pintype "passive"))
      (node (ref "U3") (pin "44") (pinfunction "PF11-BOOT0_44") (pintype "bidirectional"))
    )
    (net (code "2") (name "/BTN") (class "Default")
      (node (ref "C15") (pin "1") (pintype "passive"))
      (node (ref "R11") (pin "1") (pintype "passive"))
      (node (ref "SW1") (pin "1") (pinfunction "1_1") (pintype "passive"))
      (node (ref "SW1") (pin "2") (pinfunction "2_2") (pintype "passive"))
      (node (ref "U3") (pin "14") (pinfunction "PA4_14") (pintype "bidirectional"))
    )
    (net (code "3") (name "/CAN_RX") (class "Default")
      (node (ref "U3") (pin "45") (pinfunction "PB8_45") (pintype "bidirectional"))
      (node (ref "U5") (pin "4") (pinfunction "RXD_4") (pintype "output"))
    )
    (net (code "4") (name "/CAN_STBY") (class "Default")
      (node (ref "U3") (pin "15") (pinfunction "PA5_15") (pintype "bidirectional"))
      (node (ref "U5") (pin "8") (pinfunction "STBY_8") (pintype "input"))
    )
    (net (code "5") (name "/CAN_TX") (class "Default")
      (node (ref "U3") (pin "46") (pinfunction "PB9_46") (pintype "bidirectional"))
      (node (ref "U5") (pin "1") (pinfunction "TXD_1") (pintype "input"))
    )
    (net (code "6") (name "/CS") (class "Default")
      (node (ref "C30") (pin "1") (pintype "passive"))
      (node (ref "R28") (pin "2") (pintype "passive"))
      (node (ref "U3") (pin "10") (pinfunction "PA0_10") (pintype "bidirectional"))
    )
    (net (code "7") (name "/ENC_A") (class "Default")
      (node (ref "R24") (pin "1") (pintype "passive"))
      (node (ref "U3") (pin "38") (pinfunction "PA15_38") (pintype "bidirectional"))
    )
    (net (code "8") (name "/ENC_B") (class "Default")
      (node (ref "R25") (pin "1") (pintype "passive"))
      (node (ref "U3") (pin "39") (pinfunction "PB3_39") (pintype "bidirectional"))
    )
    (net (code "9") (name "/I2C1_SCL") (class "Default")
      (node (ref "P5") (pin "3") (pinfunction "3_3") (pintype "passive"))
      (node (ref "R1") (pin "2") (pintype "passive"))
      (node (ref "U3") (pin "21") (pinfunction "PB10_21") (pintype "bidirectional"))
    )
    (net (code "10") (name "/I2C1_SDA") (class "Default")
      (node (ref "P5") (pin "4") (pinfunction "4_4") (pintype "passive"))
      (node (ref "R2") (pin "2") (pintype "passive"))
      (node (ref "U3") (pin "22") (pinfunction "PB11_22") (pintype "bidirectional"))
    )
    (net (code "11") (name "/INA") (class "Default")
      (node (ref "R18") (pin "1") (pintype "passive"))
      (node (ref "U3") (pin "30") (pinfunction "PA9_30") (pintype "bidirectional"))
    )
    (net (code "12") (name "/INB") (class "Default")
      (node (ref "R19") (pin "1") (pintype "passive"))
      (node (ref "U3") (pin "31") (pinfunction "PA10_31") (pintype "bidirectional"))
    )
    (net (code "13") (name "/LED_B") (class "Default")
      (node (ref "R17") (pin "1") (pintype "passive"))
      (node (ref "U3") (pin "16") (pinfunction "PA6_16") (pintype "bidirectional"))
    )
    (net (code "14") (name "/LED_G") (class "Default")
      (node (ref "R15") (pin "1") (pintype "passive"))
      (node (ref "U3") (pin "17") (pinfunction "PA7_17") (pintype "bidirectional"))
    )
    (net (code "15") (name "/LED_R") (class "Default")
      (node (ref "R12") (pin "1") (pintype "passive"))
      (node (ref "U3") (pin "18") (pinfunction "PB0_18") (pintype "bidirectional"))
    )
    (net (code "16") (name "/MASTER") (class "Default")
      (node (ref "K3") (pin "1") (pintype "passive"))
      (node (ref "R33") (pin "2") (pintype "passive"))
      (node (ref "U3") (pin "40") (pinfunction "PB4_40") (pintype "bidirectional"))
    )
    (net (code "17") (name "/MOT+") (class "Default")
      (node (ref "P6") (pin "1") (pinfunction "1_1") (pintype "passive"))
      (node (ref "P7") (pin "1") (pinfunction "1_1") (pintype "passive"))
      (node (ref "U4") (pin "15") (pinfunction "OUTA_15") (pintype "output"))
      (node (ref "U4") (pin "2") (pinfunction "OUTA_2") (pintype "output"))
    )
    (net (code "18") (name "/MOT-") (class "Default")
      (node (ref "P6") (pin "2") (pinfunction "2_2") (pintype "passive"))
      (node (ref "P7") (pin "2") (pinfunction "2_2") (pintype "passive"))
      (node (ref "U4") (pin "10") (pinfunction "OUTB_10") (pintype "output"))
      (node (ref "U4") (pin "7") (pinfunction "OUTB_7") (pintype "output"))
    )
    (net (code "19") (name "/NRST") (class "Default")
      (node (ref "C17") (pin "1") (pintype "passive"))
      (node (ref "R13") (pin "1") (pintype "passive"))
      (node (ref "R37") (pin "1") (pintype "passive"))
      (node (ref "SW2") (pin "1") (pinfunction "1_1") (pintype "passive"))
      (node (ref "SW2") (pin "2") (pinfunction "2_2") (pintype "passive"))
      (node (ref "U3") (pin "7") (pinfunction "NRST_7") (pintype "bidirectional"))
    )
    (net (code "20") (name "/PWM") (class "Default")
      (node (ref "R20") (pin "1") (pintype "passive"))
      (node (ref "U3") (pin "29") (pinfunction "PA8_29") (pintype "bidirectional"))
    )
    (net (code "21") (name "/SEL0") (class "Default")
      (node (ref "R22") (pin "1") (pintype "passive"))
      (node (ref "U3") (pin "13") (pinfunction "PA3_13") (pintype "bidirectional"))
    )
    (net (code "22") (name "/SLAVE") (class "Default")
      (node (ref "K3") (pin "3") (pintype "passive"))
      (node (ref "R34") (pin "2") (pintype "passive"))
      (node (ref "U3") (pin "41") (pinfunction "PB5_41") (pintype "bidirectional"))
    )
    (net (code "23") (name "/SPI_CS") (class "Default")
      (node (ref "R32") (pin "1") (pintype "passive"))
      (node (ref "U3") (pin "25") (pinfunction "PB12_25") (pintype "bidirectional"))
    )
    (net (code "24") (name "/SPI_MISO") (class "Default")
      (node (ref "R30") (pin "1") (pintype "passive"))
      (node (ref "U3") (pin "27") (pinfunction "PB14_27") (pintype "bidirectional"))
    )
    (net (code "25") (name "/SPI_MOSI") (class "Default")
      (node (ref "R29") (pin "1") (pintype "passive"))
      (node (ref "U3") (pin "28") (pinfunction "PB15_28") (pintype "bidirectional"))
    )
    (net (code "26") (name "/SPI_SCLK") (class "Default")
      (node (ref "R31") (pin "1") (pintype "passive"))
      (node (ref "U3") (pin "26") (pinfunction "PB13_26") (pintype "bidirectional"))
    )
    (net (code "27") (name "/SWCLK") (class "Default")
      (node (ref "R35") (pin "1") (pintype "passive"))
      (node (ref "U3") (pin "37") (pinfunction "PA14_37") (pintype "bidirectional"))
    )
    (net (code "28") (name "/SWDIO") (class "Default")
      (node (ref "R36") (pin "1") (pintype "passive"))
      (node (ref "U3") (pin "34") (pinfunction "PA13_34") (pintype "bidirectional"))
    )
    (net (code "29") (name "/UART1_RX") (class "Default")
      (node (ref "R5") (pin "1") (pintype "passive"))
      (node (ref "U3") (pin "43") (pinfunction "PB7_43") (pintype "bidirectional"))
    )
    (net (code "30") (name "/UART1_TX") (class "Default")
      (node (ref "R4") (pin "1") (pintype "passive"))
      (node (ref "U3") (pin "42") (pinfunction "PB6_42") (pintype "bidirectional"))
    )
    (net (code "31") (name "/USB_N") (class "Default")
      (node (ref "U3") (pin "32") (pinfunction "PA11_32") (pintype "bidirectional"))
      (node (ref "U6") (pin "6") (pinfunction "I/O1_6") (pintype "bidirectional"))
    )
    (net (code "32") (name "/USB_P") (class "Default")
      (node (ref "U3") (pin "33") (pinfunction "PA12_33") (pintype "bidirectional"))
      (node (ref "U6") (pin "4") (pinfunction "I/O2_4") (pintype "bidirectional"))
    )
    (net (code "33") (name "/USBx_N") (class "Default")
      (node (ref "J1") (pin "2") (pinfunction "D-_2") (pintype "passive"))
      (node (ref "U6") (pin "1") (pinfunction "I/O1_1") (pintype "bidirectional"))
    )
    (net (code "34") (name "/USBx_P") (class "Default")
      (node (ref "J1") (pin "3") (pinfunction "D+_3") (pintype "passive"))
      (node (ref "U6") (pin "3") (pinfunction "I/O2_3") (pintype "bidirectional"))
    )
    (net (code "35") (name "/VBAT_ADC") (class "Default")
      (node (ref "C18") (pin "1") (pintype "passive"))
      (node (ref "R14") (pin "2") (pintype "passive"))
      (node (ref "R16") (pin "1") (pintype "passive"))
      (node (ref "U3") (pin "12") (pinfunction "PA2_12") (pintype "bidirectional"))
    )
    (net (code "36") (name "/VBUS_SENSE") (class "Default")
      (node (ref "R10") (pin "2") (pintype "passive"))
      (node (ref "R8") (pin "2") (pintype "passive"))
      (node (ref "U3") (pin "19") (pinfunction "PB1_19") (pintype "bidirectional"))
    )
    (net (code "37") (name "/VNH_CS") (class "Default")
      (node (ref "C20") (pin "1") (pintype "passive"))
      (node (ref "R23") (pin "1") (pintype "passive"))
      (node (ref "U3") (pin "11") (pinfunction "PA1_11") (pintype "bidirectional"))
    )
    (net (code "38") (name "5V") (class "Default")
      (node (ref "C3") (pin "1") (pintype "passive"))
      (node (ref "C4") (pin "1") (pintype "passive"))
      (node (ref "C6") (pin "1") (pintype "passive"))
      (node (ref "C7") (pin "1") (pintype "passive"))
      (node (ref "C8") (pin "1") (pintype "passive"))
      (node (ref "D1") (pin "A") (pinfunction "A_A") (pintype "passive"))
      (node (ref "D3") (pin "K") (pinfunction "K_K") (pintype "passive"))
      (node (ref "P4") (pin "1") (pinfunction "1_1") (pintype "passive"))
      (node (ref "P5") (pin "1") (pinfunction "1_1") (pintype "passive"))
      (node (ref "P7") (pin "4") (pinfunction "4_4") (pintype "passive"))
      (node (ref "U1") (pin "3") (pinfunction "VOUT_3") (pintype "power_in"))
      (node (ref "U2") (pin "3") (pinfunction "VIN_3") (pintype "power_in"))
      (node (ref "U5") (pin "3") (pinfunction "VCC_3") (pintype "power_in"))
    )
    (net (code "39") (name "GND") (class "Default")
      (node (ref "C1") (pin "2") (pintype "passive"))
      (node (ref "C10") (pin "2") (pintype "passive"))
      (node (ref "C11") (pin "2") (pintype "passive"))
      (node (ref "C12") (pin "2") (pintype "passive"))
      (node (ref "C13") (pin "2") (pintype "passive"))
      (node (ref "C14") (pin "2") (pintype "passive"))
      (node (ref "C15") (pin "2") (pintype "passive"))
      (node (ref "C16") (pin "1") (pintype "passive"))
      (node (ref "C17") (pin "2") (pintype "passive"))
      (node (ref "C18") (pin "2") (pintype "passive"))
      (node (ref "C19") (pin "1") (pintype "passive"))
      (node (ref "C2") (pin "2") (pintype "passive"))
      (node (ref "C20") (pin "2") (pintype "passive"))
      (node (ref "C21") (pin "2") (pintype "passive"))
      (node (ref "C22") (pin "2") (pintype "passive"))
      (node (ref "C23") (pin "2") (pintype "passive"))
      (node (ref "C24") (pin "2") (pintype "passive"))
      (node (ref "C25") (pin "2") (pintype "passive"))
      (node (ref "C26") (pin "2") (pintype "passive"))
      (node (ref "C27") (pin "2") (pintype "passive"))
      (node (ref "C28") (pin "2") (pintype "passive"))
      (node (ref "C29") (pin "2") (pintype "passive"))
      (node (ref "C3") (pin "2") (pintype "passive"))
      (node (ref "C30") (pin "2") (pintype "passive"))
      (node (ref "C31") (pin "2") (pintype "passive"))
      (node (ref "C32") (pin "2") (pintype "passive"))
      (node (ref "C33") (pin "2") (pintype "passive"))
      (node (ref "C34") (pin "2") (pinfunction "2_2") (pintype "passive"))
      (node (ref "C35") (pin "2") (pinfunction "2_2") (pintype "passive"))
      (node (ref "C36") (pin "2") (pintype "passive"))
      (node (ref "C4") (pin "2") (pintype "passive"))
      (node (ref "C5") (pin "2") (pintype "passive"))
      (node (ref "C6") (pin "2") (pintype "passive"))
      (node (ref "C7") (pin "2") (pintype "passive"))
      (node (ref "C8") (pin "2") (pintype "passive"))
      (node (ref "C9") (pin "2") (pintype "passive"))
      (node (ref "D4") (pin "A") (pinfunction "A_A") (pintype "passive"))
      (node (ref "D5") (pin "KB") (pinfunction "K_KB") (pintype "passive"))
      (node (ref "D5") (pin "KG") (pinfunction "K_KG") (pintype "passive"))
      (node (ref "D5") (pin "KR") (pinfunction "K_KR") (pintype "passive"))
      (node (ref "H1") (pin "0") (pinfunction "0_0") (pintype "passive"))
      (node (ref "H2") (pin "0") (pinfunction "0_0") (pintype "passive"))
      (node (ref "H3") (pin "0") (pinfunction "0_0") (pintype "passive"))
      (node (ref "H4") (pin "0") (pinfunction "0_0") (pintype "passive"))
      (node (ref "J1") (pin "5") (pinfunction "GND_5") (pintype "passive"))
      (node (ref "J1") (pin "SH") (pinfunction "Shell_SH") (pintype "passive"))
      (node (ref "P1") (pin "2") (pinfunction "2_2") (pintype "passive"))
      (node (ref "P2") (pin "3") (pinfunction "3_3") (pintype "passive"))
      (node (ref "P3") (pin "6") (pinfunction "6_6") (pintype "passive"))
      (node (ref "P4") (pin "5") (pinfunction "5_5") (pintype "passive"))
      (node (ref "P5") (pin "5") (pinfunction "5_5") (pintype "passive"))
      (node (ref "P7") (pin "3") (pinfunction "3_3") (pintype "passive"))
      (node (ref "P8") (pin "3") (pinfunction "3_3") (pintype "passive"))
      (node (ref "R10") (pin "1") (pintype "passive"))
      (node (ref "R16") (pin "2") (pintype "passive"))
      (node (ref "R21") (pin "1") (pintype "passive"))
      (node (ref "R26") (pin "2") (pintype "passive"))
      (node (ref "R27") (pin "1") (pintype "passive"))
      (node (ref "R33") (pin "1") (pintype "passive"))
      (node (ref "R34") (pin "1") (pintype "passive"))
      (node (ref "R7") (pin "2") (pintype "passive"))
      (node (ref "R9") (pin "2") (pintype "passive"))
      (node (ref "SW1") (pin "3") (pinfunction "3_3") (pintype "passive"))
      (node (ref "SW1") (pin "4") (pinfunction "4_4") (pintype "passive"))
      (node (ref "SW2") (pin "3") (pinfunction "3_3") (pintype "passive"))
      (node (ref "SW2") (pin "4") (pinfunction "4_4") (pintype "passive"))
      (node (ref "U1") (pin "2") (pinfunction "GND_2") (pintype "power_in"))
      (node (ref "U2") (pin "1") (pinfunction "GND_1") (pintype "power_in"))
      (node (ref "U3") (pin "23") (pinfunction "VSS_23") (pintype "power_in"))
      (node (ref "U3") (pin "35") (pinfunction "VSS_35") (pintype "power_in"))
      (node (ref "U3") (pin "47") (pinfunction "VSS_47") (pintype "power_in"))
      (node (ref "U3") (pin "8") (pinfunction "VSSA_8") (pintype "power_in"))
      (node (ref "U5") (pin "2") (pinfunction "GND_2") (pintype "power_in"))
      (node (ref "U5") (pin "9") (pinfunction "GND_9") (pintype "power_in"))
      (node (ref "U6") (pin "2") (pinfunction "GND_2") (pintype "power_in"))
      (node (ref "U7") (pin "2") (pinfunction "GND_2") (pintype "power_in"))
      (node (ref "U7") (pin "4") (pinfunction "IN-_4") (pintype "input"))
    )
    (net (code "40") (name "Net-(C13-Pad1)") (class "Default")
      (node (ref "C13") (pin "1") (pintype "passive"))
      (node (ref "C14") (pin "1") (pintype "passive"))
      (node (ref "D3") (pin "A") (pinfunction "A_A") (pintype "passive"))
      (node (ref "FB1") (pin "2") (pintype "passive"))
    )
    (net (code "41") (name "Net-(D5A-A)") (class "Default")
      (node (ref "D5") (pin "AR") (pinfunction "A_AR") (pintype "passive"))
      (node (ref "R12") (pin "2") (pintype "passive"))
    )
    (net (code "42") (name "Net-(D5B-A)") (class "Default")
      (node (ref "D5") (pin "AG") (pinfunction "A_AG") (pintype "passive"))
      (node (ref "R15") (pin "2") (pintype "passive"))
    )
    (net (code "43") (name "Net-(D5C-A)") (class "Default")
      (node (ref "D5") (pin "AB") (pinfunction "A_AB") (pintype "passive"))
      (node (ref "R17") (pin "2") (pintype "passive"))
    )
    (net (code "44") (name "Net-(J1-ID)") (class "Default")
      (node (ref "J1") (pin "4") (pinfunction "ID_4") (pintype "passive"))
      (node (ref "R9") (pin "1") (pintype "passive"))
    )
    (net (code "45") (name "Net-(K1-Pad2)") (class "Default")
      (node (ref "K1") (pin "2") (pintype "passive"))
      (node (ref "R3") (pin "1") (pintype "passive"))
    )
    (net (code "46") (name "Net-(P3-Pad2)") (class "Default")
      (node (ref "P3") (pin "2") (pinfunction "2_2") (pintype "passive"))
      (node (ref "R29") (pin "2") (pintype "passive"))
    )
    (net (code "47") (name "Net-(P3-Pad3)") (class "Default")
      (node (ref "P3") (pin "3") (pinfunction "3_3") (pintype "passive"))
      (node (ref "R30") (pin "2") (pintype "passive"))
    )
    (net (code "48") (name "Net-(P3-Pad4)") (class "Default")
      (node (ref "P3") (pin "4") (pinfunction "4_4") (pintype "passive"))
      (node (ref "R31") (pin "2") (pintype "passive"))
    )
    (net (code "49") (name "Net-(P3-Pad5)") (class "Default")
      (node (ref "P3") (pin "5") (pinfunction "5_5") (pintype "passive"))
      (node (ref "R32") (pin "2") (pintype "passive"))
    )
    (net (code "50") (name "Net-(P4-Pad3)") (class "Default")
      (node (ref "P4") (pin "3") (pinfunction "3_3") (pintype "passive"))
      (node (ref "R4") (pin "2") (pintype "passive"))
    )
    (net (code "51") (name "Net-(P4-Pad4)") (class "Default")
      (node (ref "P4") (pin "4") (pinfunction "4_4") (pintype "passive"))
      (node (ref "R5") (pin "2") (pintype "passive"))
    )
    (net (code "52") (name "Net-(P7-Pad5)") (class "Default")
      (node (ref "P7") (pin "5") (pinfunction "5_5") (pintype "passive"))
      (node (ref "R24") (pin "2") (pintype "passive"))
    )
    (net (code "53") (name "Net-(P7-Pad6)") (class "Default")
      (node (ref "P7") (pin "6") (pinfunction "6_6") (pintype "passive"))
      (node (ref "R25") (pin "2") (pintype "passive"))
    )
    (net (code "54") (name "Net-(P8-Pad2)") (class "Default")
      (node (ref "P8") (pin "2") (pinfunction "2_2") (pintype "passive"))
      (node (ref "R35") (pin "2") (pintype "passive"))
    )
    (net (code "55") (name "Net-(P8-Pad4)") (class "Default")
      (node (ref "P8") (pin "4") (pinfunction "4_4") (pintype "passive"))
      (node (ref "R36") (pin "2") (pintype "passive"))
    )
    (net (code "56") (name "Net-(P8-Pad5)") (class "Default")
      (node (ref "P8") (pin "5") (pinfunction "5_5") (pintype "passive"))
      (node (ref "R37") (pin "2") (pintype "passive"))
    )
    (net (code "57") (name "Net-(Q1-PadG)") (class "Default")
      (node (ref "Q1") (pin "G") (pinfunction "G_G") (pintype "passive"))
      (node (ref "R6") (pin "1") (pintype "passive"))
      (node (ref "R7") (pin "1") (pintype "passive"))
    )
    (net (code "58") (name "Net-(U1-VIN)") (class "Default")
      (node (ref "C1") (pin "1") (pintype "passive"))
      (node (ref "C2") (pin "1") (pintype "passive"))
      (node (ref "D1") (pin "K") (pinfunction "K_K") (pintype "passive"))
      (node (ref "D2") (pin "K") (pinfunction "K_K") (pintype "passive"))
      (node (ref "U1") (pin "1") (pinfunction "VIN_1") (pintype "power_in"))
    )
    (net (code "59") (name "Net-(U3-PF0-OSC_IN(PF0))") (class "Default")
      (node (ref "C16") (pin "2") (pintype "passive"))
      (node (ref "U3") (pin "5") (pinfunction "PF0-OSC_IN(PF0)_5") (pintype "bidirectional"))
      (node (ref "X1") (pin "1") (pintype "passive"))
    )
    (net (code "60") (name "Net-(U3-PF1-OSC_OUT(PF1))") (class "Default")
      (node (ref "C19") (pin "2") (pintype "passive"))
      (node (ref "U3") (pin "6") (pinfunction "PF1-OSC_OUT(PF1)_6") (pintype "bidirectional"))
      (node (ref "X1") (pin "2") (pintype "passive"))
    )
    (net (code "61") (name "Net-(U4-CS)") (class "Default")
      (node (ref "R23") (pin "2") (pintype "passive"))
      (node (ref "R26") (pin "1") (pintype "passive"))
      (node (ref "U4") (pin "13") (pinfunction "CS_13") (pintype "output"))
    )
    (net (code "62") (name "Net-(U4-INA)") (class "Default")
      (node (ref "R18") (pin "2") (pintype "passive"))
      (node (ref "U4") (pin "3") (pinfunction "INA_3") (pintype "input"))
    )
    (net (code "63") (name "Net-(U4-INB)") (class "Default")
      (node (ref "R19") (pin "2") (pintype "passive"))
      (node (ref "U4") (pin "6") (pinfunction "INB_6") (pintype "input"))
    )
    (net (code "64") (name "Net-(U4-PWM)") (class "Default")
      (node (ref "R20") (pin "2") (pintype "passive"))
      (node (ref "U4") (pin "11") (pinfunction "PWM_11") (pintype "input"))
    )
    (net (code "65") (name "Net-(U4-SEL0)") (class "Default")
      (node (ref "R22") (pin "2") (pintype "passive"))
      (node (ref "U4") (pin "14") (pinfunction "SEL0_14") (pintype "input"))
    )
    (net (code "66") (name "Net-(U5-CANH)") (class "Default")
      (node (ref "P2") (pin "2") (pinfunction "2_2") (pintype "passive"))
      (node (ref "R3") (pin "2") (pintype "passive"))
      (node (ref "U5") (pin "7") (pinfunction "CANH_7") (pintype "bidirectional"))
    )
    (net (code "67") (name "Net-(U5-CANL)") (class "Default")
      (node (ref "K1") (pin "1") (pintype "passive"))
      (node (ref "P2") (pin "1") (pinfunction "1_1") (pintype "passive"))
      (node (ref "U5") (pin "6") (pinfunction "CANL_6") (pintype "bidirectional"))
    )
    (net (code "68") (name "Net-(U7-IN+)") (class "Default")
      (node (ref "R27") (pin "2") (pintype "passive"))
      (node (ref "U4") (pin "1") (pinfunction "GNDA_1") (pintype "power_in"))
      (node (ref "U4") (pin "16") (pinfunction "GNDA_16") (pintype "power_in"))
      (node (ref "U4") (pin "8") (pinfunction "GNDB_8") (pintype "power_in"))
      (node (ref "U4") (pin "9") (pinfunction "GNDB_9") (pintype "power_in"))
      (node (ref "U7") (pin "3") (pinfunction "IN+_3") (pintype "input"))
    )
    (net (code "69") (name "Net-(U7-OUT)") (class "Default")
      (node (ref "R28") (pin "1") (pintype "passive"))
      (node (ref "U7") (pin "1") (pinfunction "OUT_1") (pintype "output"))
    )
    (net (code "70") (name "VBAT") (class "Default")
      (node (ref "P1") (pin "1") (pinfunction "1_1") (pintype "passive"))
      (node (ref "Q1") (pin "D") (pinfunction "D_D") (pintype "passive"))
    )
    (net (code "71") (name "VBUS") (class "Default")
      (node (ref "C36") (pin "1") (pintype "passive"))
      (node (ref "F1") (pin "1") (pintype "passive"))
      (node (ref "J1") (pin "1") (pinfunction "VBUS_1") (pintype "passive"))
      (node (ref "U6") (pin "5") (pinfunction "VBUS_5") (pintype "power_in"))
    )
    (net (code "72") (name "VBUS_FUSED") (class "Default")
      (node (ref "C11") (pin "1") (pintype "passive"))
      (node (ref "C12") (pin "1") (pintype "passive"))
      (node (ref "F1") (pin "2") (pintype "passive"))
      (node (ref "FB1") (pin "1") (pintype "passive"))
      (node (ref "R8") (pin "1") (pintype "passive"))
    )
    (net (code "73") (name "VCC") (class "Default")
      (node (ref "C10") (pin "1") (pintype "passive"))
      (node (ref "C21") (pin "1") (pintype "passive"))
      (node (ref "C22") (pin "1") (pintype "passive"))
      (node (ref "C23") (pin "1") (pintype "passive"))
      (node (ref "C24") (pin "1") (pintype "passive"))
      (node (ref "C25") (pin "1") (pintype "passive"))
      (node (ref "C26") (pin "1") (pintype "passive"))
      (node (ref "C27") (pin "1") (pintype "passive"))
      (node (ref "C31") (pin "1") (pintype "passive"))
      (node (ref "C5") (pin "1") (pintype "passive"))
      (node (ref "C9") (pin "1") (pintype "passive"))
      (node (ref "FB2") (pin "1") (pintype "passive"))
      (node (ref "K2") (pin "1") (pintype "passive"))
      (node (ref "K3") (pin "2") (pintype "passive"))
      (node (ref "P3") (pin "1") (pinfunction "1_1") (pintype "passive"))
      (node (ref "P4") (pin "2") (pinfunction "2_2") (pintype "passive"))
      (node (ref "P5") (pin "2") (pinfunction "2_2") (pintype "passive"))
      (node (ref "P8") (pin "1") (pinfunction "1_1") (pintype "passive"))
      (node (ref "R1") (pin "1") (pintype "passive"))
      (node (ref "R11") (pin "2") (pintype "passive"))
      (node (ref "R13") (pin "2") (pintype "passive"))
      (node (ref "R2") (pin "1") (pintype "passive"))
      (node (ref "U2") (pin "2") (pinfunction "VOUT_2") (pintype "power_in"))
      (node (ref "U2") (pin "4") (pinfunction "VOUT_4") (pintype "power_in"))
      (node (ref "U3") (pin "1") (pinfunction "VBAT_1") (pintype "power_in"))
      (node (ref "U3") (pin "24") (pinfunction "VDD_24") (pintype "power_in"))
      (node (ref "U3") (pin "36") (pinfunction "VDDIO2_36") (pintype "power_in"))
      (node (ref "U3") (pin "48") (pinfunction "VDD_48") (pintype "power_in"))
      (node (ref "U5") (pin "5") (pinfunction "VIO_5") (pintype "power_in"))
      (node (ref "U7") (pin "5") (pinfunction "VS_5") (pintype "power_in"))
    )
    (net (code "74") (name "VDDA") (class "Default")
      (node (ref "C28") (pin "1") (pintype "passive"))
      (node (ref "C29") (pin "1") (pintype "passive"))
      (node (ref "FB2") (pin "2") (pintype "passive"))
      (node (ref "U3") (pin "9") (pinfunction "VDDA_9") (pintype "power_in"))
    )
    (net (code "75") (name "VIN") (class "Default")
      (node (ref "C32") (pin "1") (pintype "passive"))
      (node (ref "C33") (pin "1") (pintype "passive"))
      (node (ref "C34") (pin "1") (pinfunction "1_1") (pintype "passive"))
      (node (ref "C35") (pin "1") (pinfunction "1_1") (pintype "passive"))
      (node (ref "D2") (pin "A") (pinfunction "A_A") (pintype "passive"))
      (node (ref "D4") (pin "K") (pinfunction "K_K") (pintype "passive"))
      (node (ref "Q1") (pin "S") (pinfunction "S_S") (pintype "passive"))
      (node (ref "R14") (pin "1") (pintype "passive"))
      (node (ref "R6") (pin "2") (pintype "passive"))
      (node (ref "U4") (pin "12") (pinfunction "VCC_12") (pintype "power_in"))
      (node (ref "U4") (pin "4") (pinfunction "VCC_4") (pintype "power_in"))
      (node (ref "U4") (pin "5") (pinfunction "VCC_5") (pintype "power_in"))
    )
    (net (code "76") (name "unconnected-(U3-PB2-Pad20)") (class "Default")
      (node (ref "U3") (pin "20") (pinfunction "PB2_20") (pintype "bidirectional"))
    )
    (net (code "77") (name "unconnected-(U3-PC13-Pad2)") (class "Default")
      (node (ref "U3") (pin "2") (pinfunction "PC13_2") (pintype "bidirectional"))
    )
    (net (code "78") (name "unconnected-(U3-PC14-OSC32_IN(PC14)-Pad3)") (class "Default")
      (node (ref "U3") (pin "3") (pinfunction "PC14-OSC32_IN(PC14)_3") (pintype "bidirectional"))
    )
    (net (code "79") (name "unconnected-(U3-PC15-OSC32_OUT(PC15)-Pad4)") (class "Default")
      (node (ref "U3") (pin "4") (pinfunction "PC15-OSC32_OUT(PC15)_4") (pintype "bidirectional"))
    )
  )
)
